# Holder_PCB_V2.net
KiCad netlist of a schematic drawn in Altium Designer
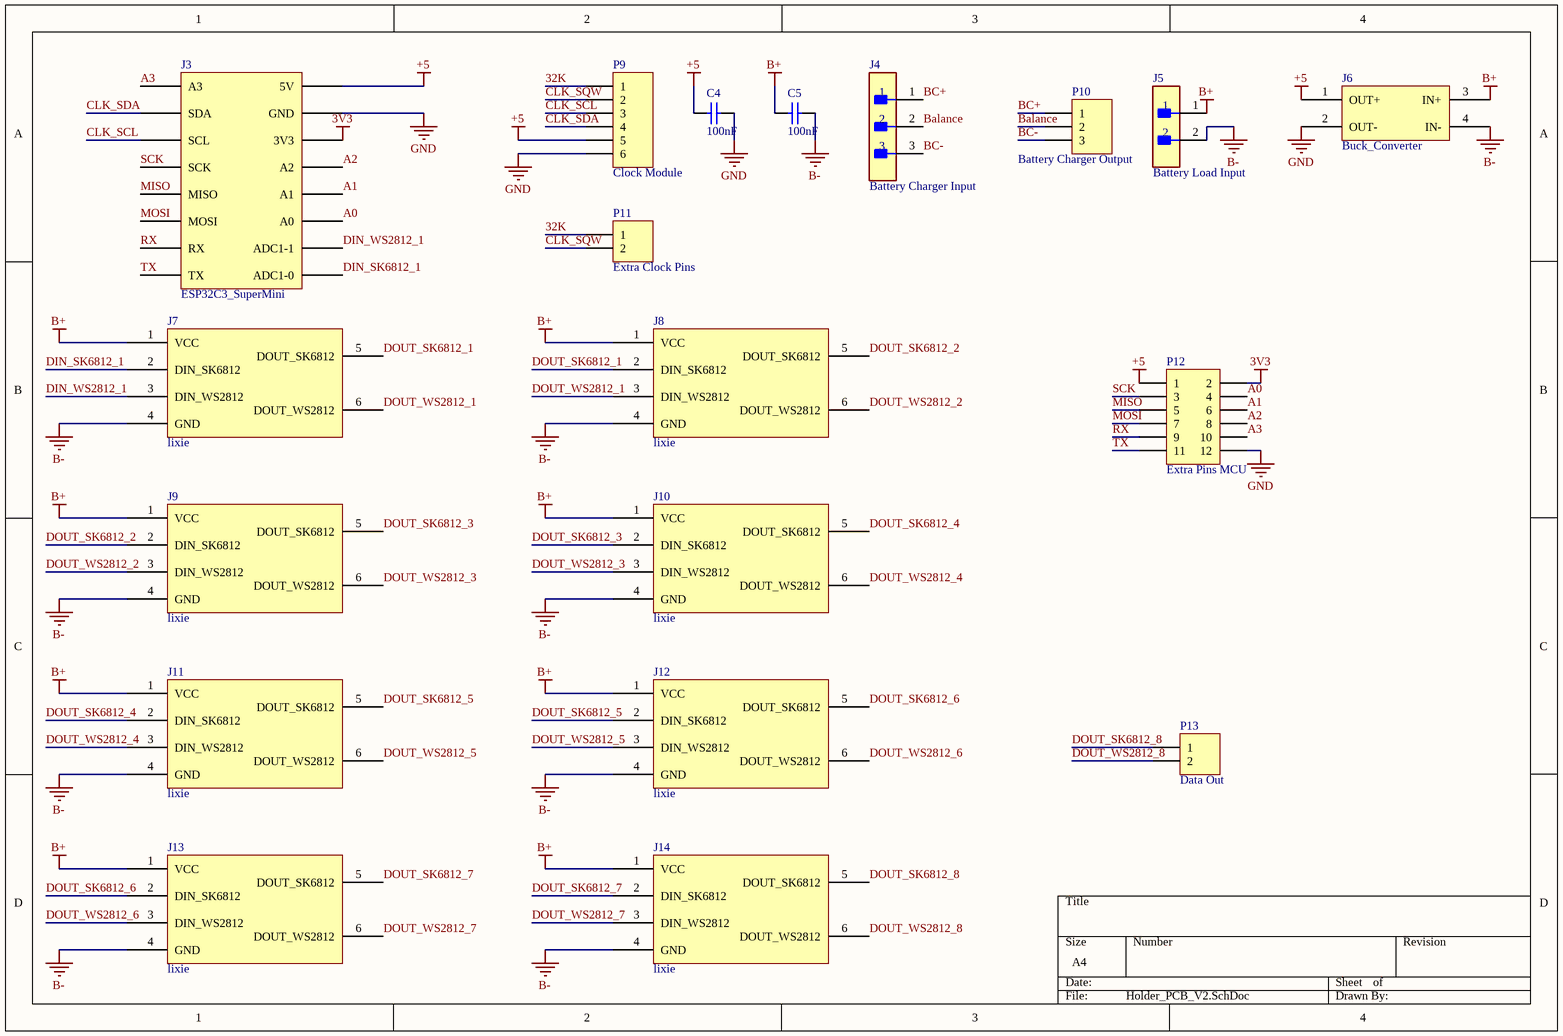
[diagram p0: Holder_PCB_V2.SchDoc]

(export (version "E")
  (design (tool "Eeschema 10.0.6"))
  (components
    (comp (ref "C4")
      (value "100nF")
      (footprint "0805C")
      (description "Capacitor")
      (fields (field (name "REVIEWED BY") "RM - 2018/08/05"))
      (libsource (lib "DSO") (part "C"))
    )
    (comp (ref "C5")
      (value "100nF")
      (footprint "0805C")
      (description "Capacitor")
      (fields (field (name "REVIEWED BY") "RM - 2018/08/05"))
      (libsource (lib "DSO") (part "C"))
    )
    (comp (ref "J3")
      (value "ESP32C3_SuperMini")
      (footprint "ESP32C3_SuperMini")
      (libsource (lib "Schlib") (part "ESP32C3_SuperMini"))
    )
    (comp (ref "J4")
      (value "Battery Charger Input")
      (footprint "FP-B3B-XH-A_LF_SN-MFG")
      (description "CONN HEADER VERT 3POS 2.5MM")
      (libsource (lib "Altium Content Vault") (part "0d3f023dd272f625e17a2be33dea85f"))
    )
    (comp (ref "J5")
      (value "Battery Load Input")
      (footprint "FP-B2B-XH-A_LF_SN-MFG")
      (description "CONN HEADER VERT 2POS 2.5MM")
      (libsource (lib "Altium Content Vault") (part "3bc925449376181038e59eaffc5286c"))
    )
    (comp (ref "J6")
      (value "Buck_Converter")
      (footprint "Buck_Converter")
      (libsource (lib "Schlib") (part "Buck_Converter"))
    )
    (comp (ref "J7") (value "lixie") (footprint "Lixie") (libsource (lib "Schlib") (part "lixie")))
    (comp (ref "J8") (value "lixie") (footprint "Lixie") (libsource (lib "Schlib") (part "lixie")))
    (comp (ref "J9") (value "lixie") (footprint "Lixie") (libsource (lib "Schlib") (part "lixie")))
    (comp (ref "J10") (value "lixie") (footprint "Lixie") (libsource (lib "Schlib") (part "lixie")))
    (comp (ref "J11") (value "lixie") (footprint "Lixie") (libsource (lib "Schlib") (part "lixie")))
    (comp (ref "J12") (value "lixie") (footprint "Lixie") (libsource (lib "Schlib") (part "lixie")))
    (comp (ref "J13") (value "lixie") (footprint "Lixie") (libsource (lib "Schlib") (part "lixie")))
    (comp (ref "J14") (value "lixie") (footprint "Lixie") (libsource (lib "Schlib") (part "lixie")))
    (comp (ref "P9")
      (value "Clock Module")
      (footprint "HDR1X6")
      (description "Header, 6-Pin")
      (fields (field (name "PUBLISHER") "Altium Limited"))
      (libsource (lib "Miscellaneous Connectors") (part "Header 6"))
    )
    (comp (ref "P10")
      (value "Battery Charger Output")
      (footprint "HDR1X3")
      (description "Header, 3-Pin")
      (fields (field (name "PUBLISHER") "Altium Limited"))
      (libsource (lib "Miscellaneous Connectors") (part "Header 3"))
    )
    (comp (ref "P11")
      (value "Extra Clock Pins")
      (footprint "HDR1X2")
      (description "Header, 2-Pin")
      (fields (field (name "PUBLISHER") "Altium Limited"))
      (libsource (lib "Miscellaneous Connectors") (part "Header 2"))
    )
    (comp (ref "P12")
      (value "Extra Pins MCU")
      (footprint "HDR2X6")
      (description "Header, 6-Pin, Dual row")
      (fields (field (name "PUBLISHER") "Altium Limited"))
      (libsource (lib "Miscellaneous Connectors") (part "Header 6X2"))
    )
    (comp (ref "P13")
      (value "Data Out")
      (footprint "HDR1X2")
      (description "Header, 2-Pin")
      (fields (field (name "PUBLISHER") "Altium Limited"))
      (libsource (lib "Miscellaneous Connectors") (part "Header 2"))
    )
  )
  (nets
    (net (code "1") (name "+5") (class "Default")
      (node (ref "C4") (pin "2") (pinfunction "2_2") (pintype "passive"))
      (node (ref "J3") (pin "5V") (pinfunction "5V_5V") (pintype "passive"))
      (node (ref "J6") (pin "1") (pinfunction "OUT+_1") (pintype "passive"))
      (node (ref "P12") (pin "1") (pinfunction "1_1") (pintype "passive"))
      (node (ref "P9") (pin "5") (pinfunction "5_5") (pintype "passive"))
    )
    (net (code "2") (name "/32K") (class "Default")
      (node (ref "P11") (pin "1") (pinfunction "1_1") (pintype "passive"))
      (node (ref "P9") (pin "1") (pinfunction "1_1") (pintype "passive"))
    )
    (net (code "3") (name "/A0") (class "Default")
      (node (ref "J3") (pin "2") (pinfunction "A0_2") (pintype "passive"))
      (node (ref "P12") (pin "4") (pinfunction "4_4") (pintype "passive"))
    )
    (net (code "4") (name "/A1") (class "Default")
      (node (ref "J3") (pin "3") (pinfunction "A1_3") (pintype "passive"))
      (node (ref "P12") (pin "6") (pinfunction "6_6") (pintype "passive"))
    )
    (net (code "5") (name "/A2") (class "Default")
      (node (ref "J3") (pin "4") (pinfunction "A2_4") (pintype "passive"))
      (node (ref "P12") (pin "8") (pinfunction "8_8") (pintype "passive"))
    )
    (net (code "6") (name "/A3") (class "Default")
      (node (ref "J3") (pin "5") (pinfunction "A3_5") (pintype "passive"))
      (node (ref "P12") (pin "10") (pinfunction "10_10") (pintype "passive"))
    )
    (net (code "7") (name "/BC+") (class "Default")
      (node (ref "J4") (pin "1") (pinfunction "1_1") (pintype "passive"))
      (node (ref "P10") (pin "1") (pinfunction "1_1") (pintype "passive"))
    )
    (net (code "8") (name "/BC-") (class "Default")
      (node (ref "J4") (pin "3") (pinfunction "3_3") (pintype "passive"))
      (node (ref "P10") (pin "3") (pinfunction "3_3") (pintype "passive"))
    )
    (net (code "9") (name "/Balance") (class "Default")
      (node (ref "J4") (pin "2") (pinfunction "2_2") (pintype "passive"))
      (node (ref "P10") (pin "2") (pinfunction "2_2") (pintype "passive"))
    )
    (net (code "10") (name "/CLK_SCL") (class "Default")
      (node (ref "J3") (pin "7") (pinfunction "SCL_7") (pintype "passive"))
      (node (ref "P9") (pin "3") (pinfunction "3_3") (pintype "passive"))
    )
    (net (code "11") (name "/CLK_SDA") (class "Default")
      (node (ref "J3") (pin "6") (pinfunction "SDA_6") (pintype "passive"))
      (node (ref "P9") (pin "4") (pinfunction "4_4") (pintype "passive"))
    )
    (net (code "12") (name "/CLK_SQW") (class "Default")
      (node (ref "P11") (pin "2") (pinfunction "2_2") (pintype "passive"))
      (node (ref "P9") (pin "2") (pinfunction "2_2") (pintype "passive"))
    )
    (net (code "13") (name "/DIN_SK6812_1") (class "Default")
      (node (ref "J3") (pin "0") (pinfunction "ADC1-0_0") (pintype "passive"))
      (node (ref "J7") (pin "2") (pinfunction "DIN_SK6812_2") (pintype "passive"))
    )
    (net (code "14") (name "/DIN_WS2812_1") (class "Default")
      (node (ref "J3") (pin "1") (pinfunction "ADC1-1_1") (pintype "passive"))
      (node (ref "J7") (pin "3") (pinfunction "DIN_WS2812_3") (pintype "passive"))
    )
    (net (code "15") (name "/DOUT_SK6812_1") (class "Default")
      (node (ref "J7") (pin "5") (pinfunction "DOUT_SK6812_5") (pintype "passive"))
      (node (ref "J8") (pin "2") (pinfunction "DIN_SK6812_2") (pintype "passive"))
    )
    (net (code "16") (name "/DOUT_SK6812_2") (class "Default")
      (node (ref "J8") (pin "5") (pinfunction "DOUT_SK6812_5") (pintype "passive"))
      (node (ref "J9") (pin "2") (pinfunction "DIN_SK6812_2") (pintype "passive"))
    )
    (net (code "17") (name "/DOUT_SK6812_3") (class "Default")
      (node (ref "J10") (pin "2") (pinfunction "DIN_SK6812_2") (pintype "passive"))
      (node (ref "J9") (pin "5") (pinfunction "DOUT_SK6812_5") (pintype "passive"))
    )
    (net (code "18") (name "/DOUT_SK6812_4") (class "Default")
      (node (ref "J10") (pin "5") (pinfunction "DOUT_SK6812_5") (pintype "passive"))
      (node (ref "J11") (pin "2") (pinfunction "DIN_SK6812_2") (pintype "passive"))
    )
    (net (code "19") (name "/DOUT_SK6812_5") (class "Default")
      (node (ref "J11") (pin "5") (pinfunction "DOUT_SK6812_5") (pintype "passive"))
      (node (ref "J12") (pin "2") (pinfunction "DIN_SK6812_2") (pintype "passive"))
    )
    (net (code "20") (name "/DOUT_SK6812_6") (class "Default")
      (node (ref "J12") (pin "5") (pinfunction "DOUT_SK6812_5") (pintype "passive"))
      (node (ref "J13") (pin "2") (pinfunction "DIN_SK6812_2") (pintype "passive"))
    )
    (net (code "21") (name "/DOUT_SK6812_7") (class "Default")
      (node (ref "J13") (pin "5") (pinfunction "DOUT_SK6812_5") (pintype "passive"))
      (node (ref "J14") (pin "2") (pinfunction "DIN_SK6812_2") (pintype "passive"))
    )
    (net (code "22") (name "/DOUT_SK6812_8") (class "Default")
      (node (ref "J14") (pin "5") (pinfunction "DOUT_SK6812_5") (pintype "passive"))
      (node (ref "P13") (pin "1") (pinfunction "1_1") (pintype "passive"))
    )
    (net (code "23") (name "/DOUT_WS2812_1") (class "Default")
      (node (ref "J7") (pin "6") (pinfunction "DOUT_WS2812_6") (pintype "passive"))
      (node (ref "J8") (pin "3") (pinfunction "DIN_WS2812_3") (pintype "passive"))
    )
    (net (code "24") (name "/DOUT_WS2812_2") (class "Default")
      (node (ref "J8") (pin "6") (pinfunction "DOUT_WS2812_6") (pintype "passive"))
      (node (ref "J9") (pin "3") (pinfunction "DIN_WS2812_3") (pintype "passive"))
    )
    (net (code "25") (name "/DOUT_WS2812_3") (class "Default")
      (node (ref "J10") (pin "3") (pinfunction "DIN_WS2812_3") (pintype "passive"))
      (node (ref "J9") (pin "6") (pinfunction "DOUT_WS2812_6") (pintype "passive"))
    )
    (net (code "26") (name "/DOUT_WS2812_4") (class "Default")
      (node (ref "J10") (pin "6") (pinfunction "DOUT_WS2812_6") (pintype "passive"))
      (node (ref "J11") (pin "3") (pinfunction "DIN_WS2812_3") (pintype "passive"))
    )
    (net (code "27") (name "/DOUT_WS2812_5") (class "Default")
      (node (ref "J11") (pin "6") (pinfunction "DOUT_WS2812_6") (pintype "passive"))
      (node (ref "J12") (pin "3") (pinfunction "DIN_WS2812_3") (pintype "passive"))
    )
    (net (code "28") (name "/DOUT_WS2812_6") (class "Default")
      (node (ref "J12") (pin "6") (pinfunction "DOUT_WS2812_6") (pintype "passive"))
      (node (ref "J13") (pin "3") (pinfunction "DIN_WS2812_3") (pintype "passive"))
    )
    (net (code "29") (name "/DOUT_WS2812_7") (class "Default")
      (node (ref "J13") (pin "6") (pinfunction "DOUT_WS2812_6") (pintype "passive"))
      (node (ref "J14") (pin "3") (pinfunction "DIN_WS2812_3") (pintype "passive"))
    )
    (net (code "30") (name "/DOUT_WS2812_8") (class "Default")
      (node (ref "J14") (pin "6") (pinfunction "DOUT_WS2812_6") (pintype "passive"))
      (node (ref "P13") (pin "2") (pinfunction "2_2") (pintype "passive"))
    )
    (net (code "31") (name "/MISO") (class "Default")
      (node (ref "J3") (pin "9") (pinfunction "MISO_9") (pintype "passive"))
      (node (ref "P12") (pin "5") (pinfunction "5_5") (pintype "passive"))
    )
    (net (code "32") (name "/MOSI") (class "Default")
      (node (ref "J3") (pin "10") (pinfunction "MOSI_10") (pintype "passive"))
      (node (ref "P12") (pin "7") (pinfunction "7_7") (pintype "passive"))
    )
    (net (code "33") (name "/RX") (class "Default")
      (node (ref "J3") (pin "20") (pinfunction "RX_20") (pintype "passive"))
      (node (ref "P12") (pin "9") (pinfunction "9_9") (pintype "passive"))
    )
    (net (code "34") (name "/SCK") (class "Default")
      (node (ref "J3") (pin "8") (pinfunction "SCK_8") (pintype "passive"))
      (node (ref "P12") (pin "3") (pinfunction "3_3") (pintype "passive"))
    )
    (net (code "35") (name "/TX") (class "Default")
      (node (ref "J3") (pin "21") (pinfunction "TX_21") (pintype "passive"))
      (node (ref "P12") (pin "11") (pinfunction "11_11") (pintype "passive"))
    )
    (net (code "36") (name "3V3") (class "Default")
      (node (ref "J3") (pin "3V3") (pinfunction "3V3_3V3") (pintype "passive"))
      (node (ref "P12") (pin "2") (pinfunction "2_2") (pintype "passive"))
    )
    (net (code "37") (name "B+") (class "Default")
      (node (ref "C5") (pin "2") (pinfunction "2_2") (pintype "passive"))
      (node (ref "J10") (pin "1") (pinfunction "VCC_1") (pintype "passive"))
      (node (ref "J11") (pin "1") (pinfunction "VCC_1") (pintype "passive"))
      (node (ref "J12") (pin "1") (pinfunction "VCC_1") (pintype "passive"))
      (node (ref "J13") (pin "1") (pinfunction "VCC_1") (pintype "passive"))
      (node (ref "J14") (pin "1") (pinfunction "VCC_1") (pintype "passive"))
      (node (ref "J5") (pin "1") (pinfunction "1_1") (pintype "passive"))
      (node (ref "J6") (pin "3") (pinfunction "IN+_3") (pintype "passive"))
      (node (ref "J7") (pin "1") (pinfunction "VCC_1") (pintype "passive"))
      (node (ref "J8") (pin "1") (pinfunction "VCC_1") (pintype "passive"))
      (node (ref "J9") (pin "1") (pinfunction "VCC_1") (pintype "passive"))
    )
    (net (code "38") (name "B-") (class "Default")
      (node (ref "C5") (pin "1") (pinfunction "1_1") (pintype "passive"))
      (node (ref "J10") (pin "4") (pinfunction "GND_4") (pintype "passive"))
      (node (ref "J11") (pin "4") (pinfunction "GND_4") (pintype "passive"))
      (node (ref "J12") (pin "4") (pinfunction "GND_4") (pintype "passive"))
      (node (ref "J13") (pin "4") (pinfunction "GND_4") (pintype "passive"))
      (node (ref "J14") (pin "4") (pinfunction "GND_4") (pintype "passive"))
      (node (ref "J5") (pin "2") (pinfunction "2_2") (pintype "passive"))
      (node (ref "J6") (pin "4") (pinfunction "IN-_4") (pintype "passive"))
      (node (ref "J7") (pin "4") (pinfunction "GND_4") (pintype "passive"))
      (node (ref "J8") (pin "4") (pinfunction "GND_4") (pintype "passive"))
      (node (ref "J9") (pin "4") (pinfunction "GND_4") (pintype "passive"))
    )
    (net (code "39") (name "GND") (class "Default")
      (node (ref "C4") (pin "1") (pinfunction "1_1") (pintype "passive"))
      (node (ref "J3") (pin "GND") (pinfunction "GND_GND") (pintype "passive"))
      (node (ref "J6") (pin "2") (pinfunction "OUT-_2") (pintype "passive"))
      (node (ref "P12") (pin "12") (pinfunction "12_12") (pintype "passive"))
      (node (ref "P9") (pin "6") (pinfunction "6_6") (pintype "passive"))
    )
  )
)
